# P14_Hi3531AV100_SATA_PC.net
KiCad netlist of a schematic drawn in Altium Designer
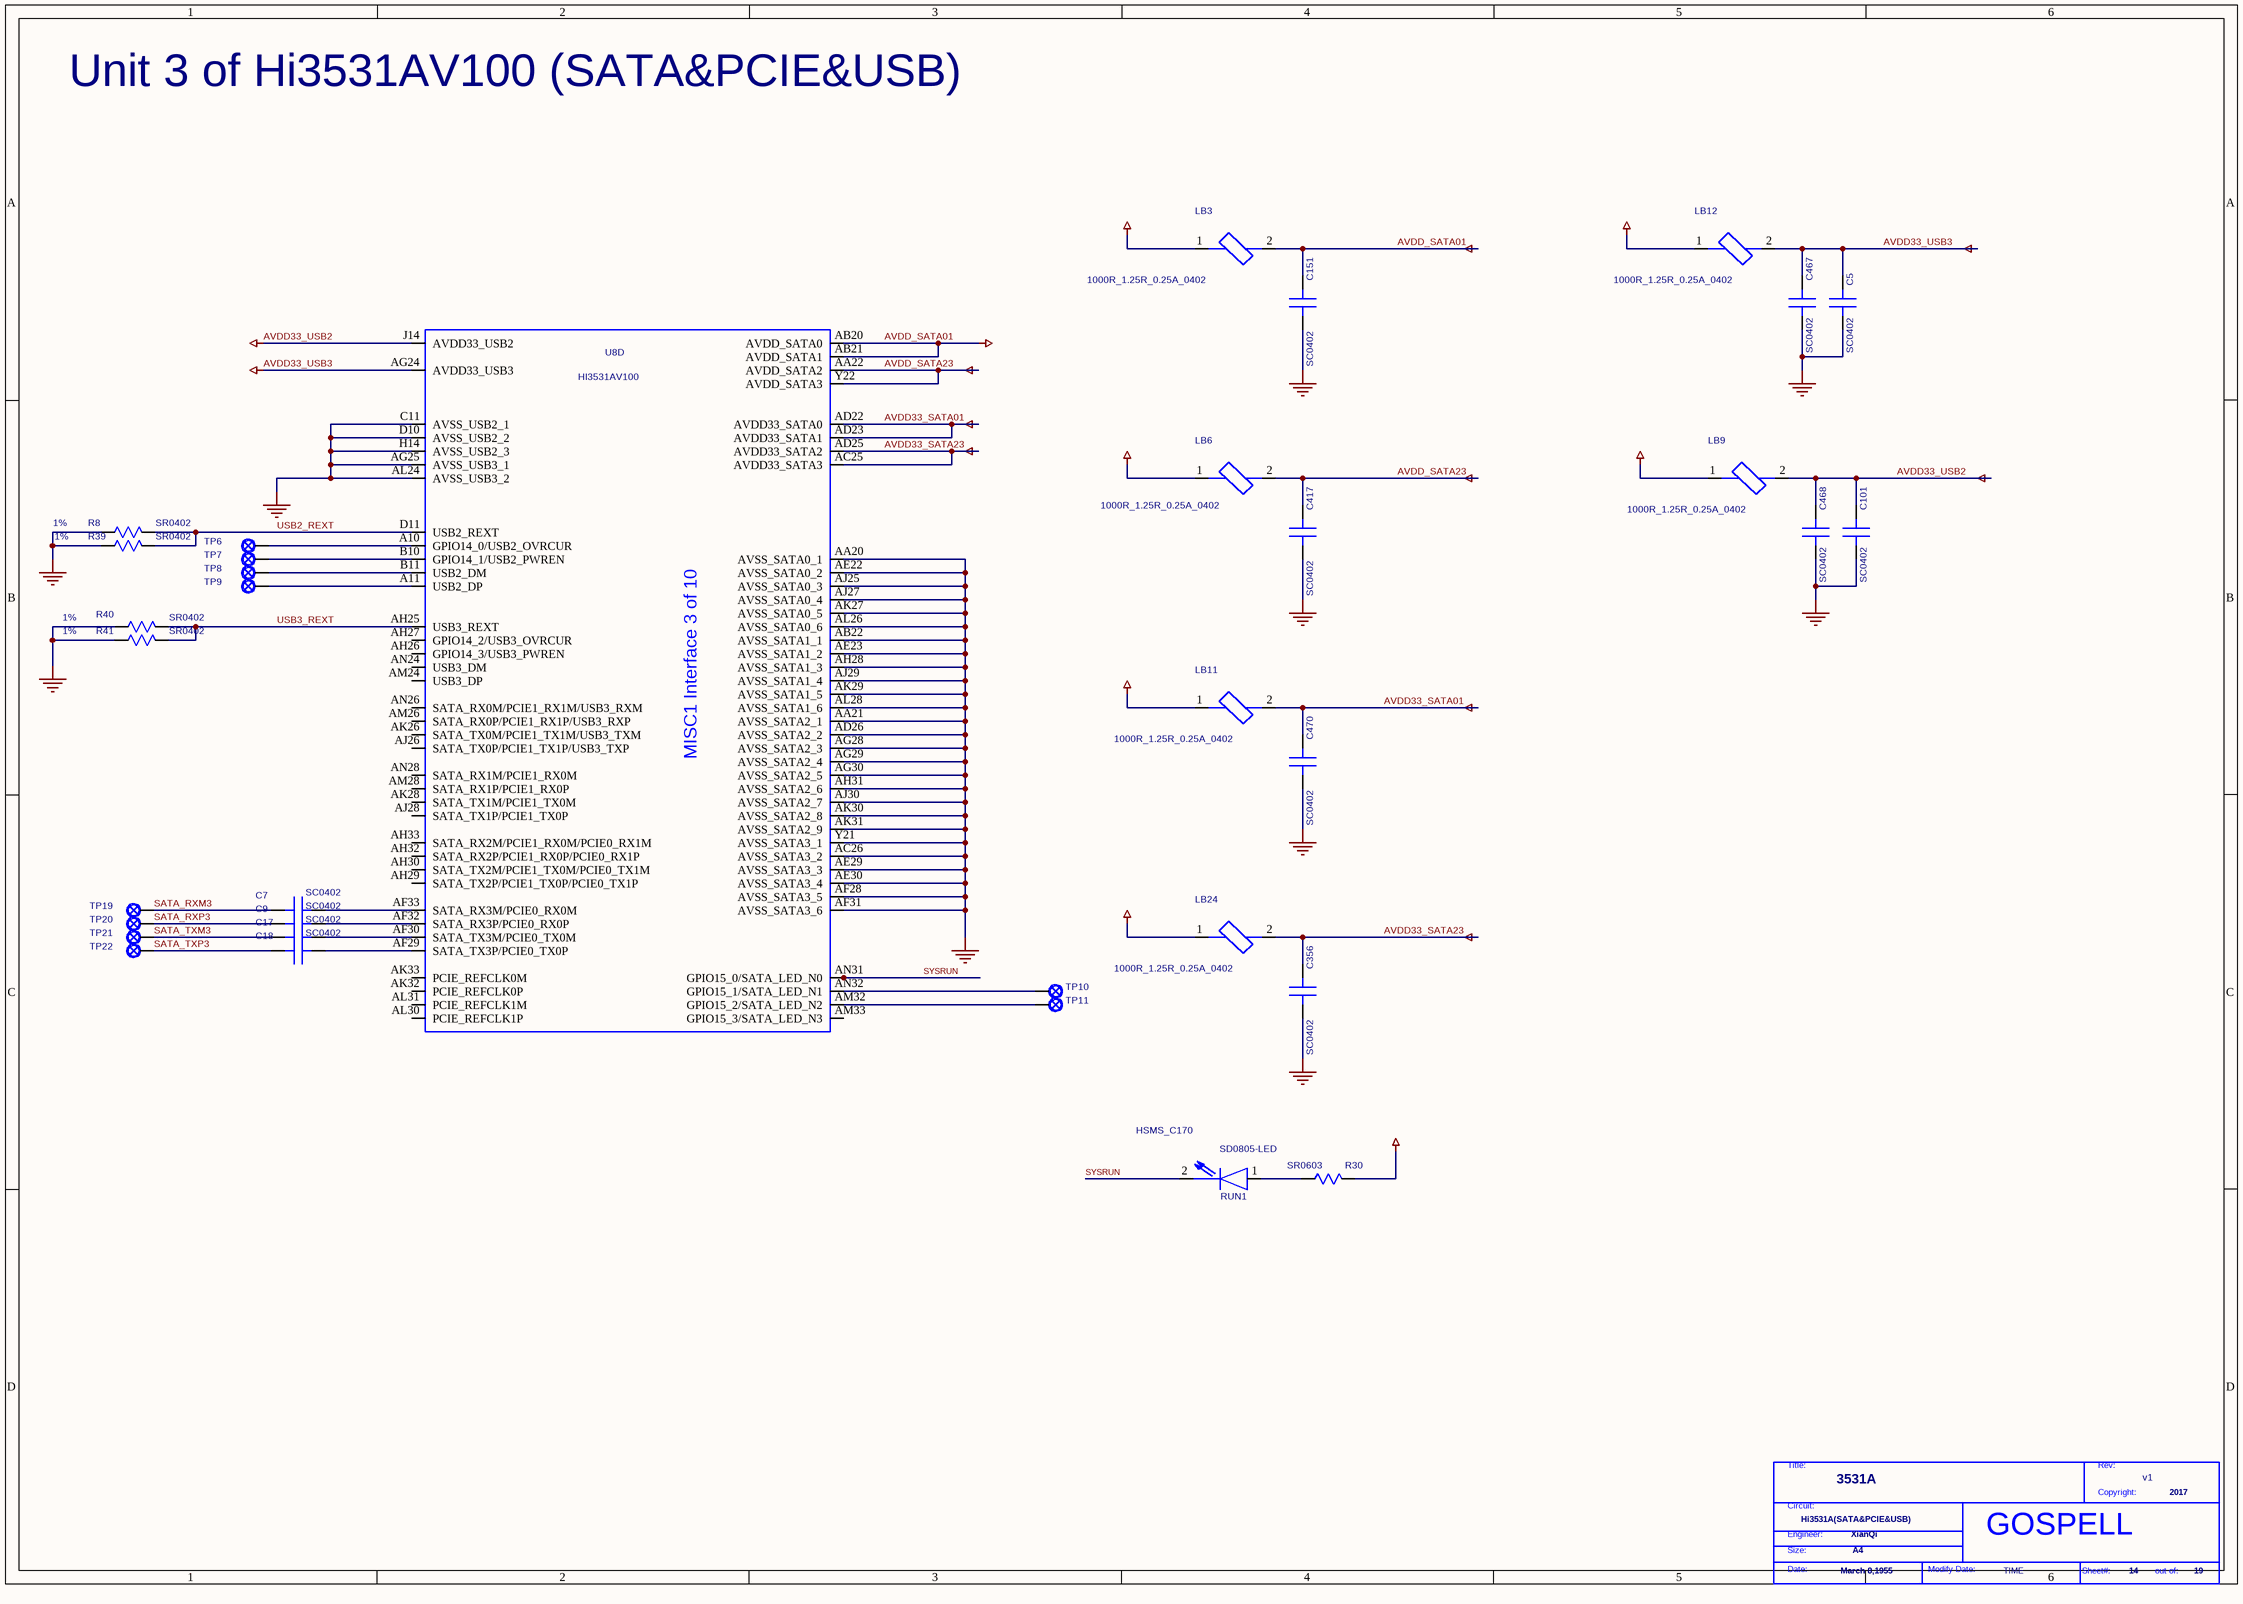
[diagram p0: P14 Hi3531AV100(SATA&PC.SchDoc]

(export (version "E")
  (design (tool "Eeschema 10.0.6"))
  (components
    (comp (ref "C5") (value "SC0402") (libsource (lib "*") (part "C_0_Dup2")))
    (comp (ref "C7") (value "SC0402") (libsource (lib "*") (part "C_0_Dup2")))
    (comp (ref "C9") (value "SC0402") (libsource (lib "*") (part "C_0_Dup2")))
    (comp (ref "C17") (value "SC0402") (libsource (lib "*") (part "C_0_Dup2")))
    (comp (ref "C18") (value "SC0402") (libsource (lib "*") (part "C_0_Dup2")))
    (comp (ref "C101") (value "SC0402") (libsource (lib "*") (part "C_0_Dup2")))
    (comp (ref "C151") (value "SC0402") (libsource (lib "*") (part "C_0_Dup2")))
    (comp (ref "C356") (value "SC0402") (libsource (lib "*") (part "C_0_Dup2")))
    (comp (ref "C417") (value "SC0402") (libsource (lib "*") (part "C_0_Dup2")))
    (comp (ref "C467") (value "SC0402") (libsource (lib "*") (part "C_0_Dup2")))
    (comp (ref "C468") (value "SC0402") (libsource (lib "*") (part "C_0_Dup2")))
    (comp (ref "C470") (value "SC0402") (libsource (lib "*") (part "C_0_Dup2")))
    (comp (ref "LB3") (value "SL0402") (libsource (lib "*") (part "LB_0")))
    (comp (ref "LB6") (value "SL0402") (libsource (lib "*") (part "LB_0")))
    (comp (ref "LB9") (value "SL0402") (libsource (lib "*") (part "LB_0")))
    (comp (ref "LB11") (value "SL0402") (libsource (lib "*") (part "LB_0")))
    (comp (ref "LB12") (value "SL0402") (libsource (lib "*") (part "LB_0")))
    (comp (ref "LB24") (value "SL0402") (libsource (lib "*") (part "LB_0")))
    (comp (ref "R8") (value "SR0402") (libsource (lib "*") (part "R_1")))
    (comp (ref "R30") (value "SR0603") (libsource (lib "*") (part "R_1")))
    (comp (ref "R39") (value "SR0402") (libsource (lib "*") (part "R_1")))
    (comp (ref "R40") (value "SR0402") (libsource (lib "*") (part "R_1")))
    (comp (ref "R41") (value "SR0402") (libsource (lib "*") (part "R_1")))
    (comp (ref "RUN1")
      (value "SD0805-LED")
      (fields (field (name "DEVICE") "HSMS_C170"))
      (libsource (lib "*") (part "LED_1"))
    )
    (comp (ref "TP6") (value "TP24-SMD") (libsource (lib "*") (part "TESTPOINT_0")))
    (comp (ref "TP7") (value "TP24-SMD") (libsource (lib "*") (part "TESTPOINT_0")))
    (comp (ref "TP8") (value "TP24-SMD") (libsource (lib "*") (part "TESTPOINT_0")))
    (comp (ref "TP9") (value "TP24-SMD") (libsource (lib "*") (part "TESTPOINT_0")))
    (comp (ref "TP10") (value "TP24-SMD") (libsource (lib "*") (part "TESTPOINT_0")))
    (comp (ref "TP11") (value "TP24-SMD") (libsource (lib "*") (part "TESTPOINT_0")))
    (comp (ref "TP19") (value "TP24-SMD") (libsource (lib "*") (part "TESTPOINT_0")))
    (comp (ref "TP20") (value "TP24-SMD") (libsource (lib "*") (part "TESTPOINT_0")))
    (comp (ref "TP21") (value "TP24-SMD") (libsource (lib "*") (part "TESTPOINT_0")))
    (comp (ref "TP22") (value "TP24-SMD") (libsource (lib "*") (part "TESTPOINT_0")))
    (comp (ref "U8")
      (value "BGA805-32-3333")
      (fields (field (name "DEVICE") "HI3531AV100"))
      (libsource (lib "*") (part "HI3531AV100_M2_17"))
    )
  )
  (nets
    (net (code "1") (name "/SATA_RXM3") (class "Default")
      (node (ref "C7") (pin "1") (pinfunction "A_1") (pintype "passive"))
      (node (ref "TP19") (pin "1") (pinfunction "1_1") (pintype "passive"))
    )
    (net (code "2") (name "/SATA_RXP3") (class "Default")
      (node (ref "C9") (pin "1") (pinfunction "A_1") (pintype "passive"))
      (node (ref "TP20") (pin "1") (pinfunction "1_1") (pintype "passive"))
    )
    (net (code "3") (name "/SATA_TXM3") (class "Default")
      (node (ref "C17") (pin "1") (pinfunction "A_1") (pintype "passive"))
      (node (ref "TP21") (pin "1") (pinfunction "1_1") (pintype "passive"))
    )
    (net (code "4") (name "/SATA_TXP3") (class "Default")
      (node (ref "C18") (pin "1") (pinfunction "A_1") (pintype "passive"))
      (node (ref "TP22") (pin "1") (pinfunction "1_1") (pintype "passive"))
    )
    (net (code "5") (name "/SYSRUN") (class "Default")
      (node (ref "RUN1") (pin "2") (pinfunction "B_2") (pintype "passive"))
      (node (ref "U8") (pin "AN31") (pinfunction "GPIO15_0/SATA_LED_N0_AN31") (pintype "passive"))
    )
    (net (code "6") (name "/USB2_REXT") (class "Default")
      (node (ref "R39") (pin "2") (pinfunction "B_2") (pintype "passive"))
      (node (ref "R8") (pin "2") (pinfunction "B_2") (pintype "passive"))
      (node (ref "U8") (pin "D11") (pinfunction "USB2_REXT_D11") (pintype "passive"))
    )
    (net (code "7") (name "/USB3_REXT") (class "Default")
      (node (ref "R40") (pin "2") (pinfunction "B_2") (pintype "passive"))
      (node (ref "R41") (pin "2") (pinfunction "B_2") (pintype "passive"))
      (node (ref "U8") (pin "AH25") (pinfunction "USB3_REXT_AH25") (pintype "passive"))
    )
    (net (code "8") (name "3V3") (class "Default")
      (node (ref "LB11") (pin "1") (pinfunction "1_1") (pintype "passive"))
      (node (ref "LB12") (pin "1") (pinfunction "1_1") (pintype "passive"))
      (node (ref "LB24") (pin "1") (pinfunction "1_1") (pintype "passive"))
      (node (ref "LB9") (pin "1") (pinfunction "1_1") (pintype "passive"))
      (node (ref "R30") (pin "1") (pinfunction "A_1") (pintype "passive"))
    )
    (net (code "9") (name "AVDD33_SATA01") (class "Default")
      (node (ref "C470") (pin "1") (pinfunction "A_1") (pintype "passive"))
      (node (ref "LB11") (pin "2") (pinfunction "2_2") (pintype "passive"))
      (node (ref "U8") (pin "AD22") (pinfunction "AVDD33_SATA0_AD22") (pintype "passive"))
      (node (ref "U8") (pin "AD23") (pinfunction "AVDD33_SATA1_AD23") (pintype "passive"))
    )
    (net (code "10") (name "AVDD33_SATA23") (class "Default")
      (node (ref "C356") (pin "1") (pinfunction "A_1") (pintype "passive"))
      (node (ref "LB24") (pin "2") (pinfunction "2_2") (pintype "passive"))
      (node (ref "U8") (pin "AC25") (pinfunction "AVDD33_SATA3_AC25") (pintype "passive"))
      (node (ref "U8") (pin "AD25") (pinfunction "AVDD33_SATA2_AD25") (pintype "passive"))
    )
    (net (code "11") (name "AVDD33_USB2") (class "Default")
      (node (ref "C101") (pin "1") (pinfunction "A_1") (pintype "passive"))
      (node (ref "C468") (pin "1") (pinfunction "A_1") (pintype "passive"))
      (node (ref "LB9") (pin "2") (pinfunction "2_2") (pintype "passive"))
      (node (ref "U8") (pin "J14") (pinfunction "AVDD33_USB2_J14") (pintype "passive"))
    )
    (net (code "12") (name "AVDD33_USB3") (class "Default")
      (node (ref "C467") (pin "1") (pinfunction "A_1") (pintype "passive"))
      (node (ref "C5") (pin "1") (pinfunction "A_1") (pintype "passive"))
      (node (ref "LB12") (pin "2") (pinfunction "2_2") (pintype "passive"))
      (node (ref "U8") (pin "AG24") (pinfunction "AVDD33_USB3_AG24") (pintype "passive"))
    )
    (net (code "13") (name "AVDD_SATA01") (class "Default")
      (node (ref "C151") (pin "1") (pinfunction "A_1") (pintype "passive"))
      (node (ref "LB3") (pin "2") (pinfunction "2_2") (pintype "passive"))
      (node (ref "U8") (pin "AB20") (pinfunction "AVDD_SATA0_AB20") (pintype "passive"))
      (node (ref "U8") (pin "AB21") (pinfunction "AVDD_SATA1_AB21") (pintype "passive"))
    )
    (net (code "14") (name "AVDD_SATA23") (class "Default")
      (node (ref "C417") (pin "1") (pinfunction "A_1") (pintype "passive"))
      (node (ref "LB6") (pin "2") (pinfunction "2_2") (pintype "passive"))
      (node (ref "U8") (pin "AA22") (pinfunction "AVDD_SATA2_AA22") (pintype "passive"))
      (node (ref "U8") (pin "Y22") (pinfunction "AVDD_SATA3_Y22") (pintype "passive"))
    )
    (net (code "15") (name "DVDD_CORE") (class "Default")
      (node (ref "LB3") (pin "1") (pinfunction "1_1") (pintype "passive"))
      (node (ref "LB6") (pin "1") (pinfunction "1_1") (pintype "passive"))
    )
    (net (code "16") (name "GND") (class "Default")
      (node (ref "C101") (pin "2") (pinfunction "B_2") (pintype "passive"))
      (node (ref "C151") (pin "2") (pinfunction "B_2") (pintype "passive"))
      (node (ref "C356") (pin "2") (pinfunction "B_2") (pintype "passive"))
      (node (ref "C417") (pin "2") (pinfunction "B_2") (pintype "passive"))
      (node (ref "C467") (pin "2") (pinfunction "B_2") (pintype "passive"))
      (node (ref "C468") (pin "2") (pinfunction "B_2") (pintype "passive"))
      (node (ref "C470") (pin "2") (pinfunction "B_2") (pintype "passive"))
      (node (ref "C5") (pin "2") (pinfunction "B_2") (pintype "passive"))
      (node (ref "R39") (pin "1") (pinfunction "A_1") (pintype "passive"))
      (node (ref "R40") (pin "1") (pinfunction "A_1") (pintype "passive"))
      (node (ref "R41") (pin "1") (pinfunction "A_1") (pintype "passive"))
      (node (ref "R8") (pin "1") (pinfunction "A_1") (pintype "passive"))
      (node (ref "U8") (pin "AA20") (pinfunction "AVSS_SATA0_1_AA20") (pintype "passive"))
      (node (ref "U8") (pin "AA21") (pinfunction "AVSS_SATA2_1_AA21") (pintype "passive"))
      (node (ref "U8") (pin "AB22") (pinfunction "AVSS_SATA1_1_AB22") (pintype "passive"))
      (node (ref "U8") (pin "AC26") (pinfunction "AVSS_SATA3_2_AC26") (pintype "passive"))
      (node (ref "U8") (pin "AD26") (pinfunction "AVSS_SATA2_2_AD26") (pintype "passive"))
      (node (ref "U8") (pin "AE22") (pinfunction "AVSS_SATA0_2_AE22") (pintype "passive"))
      (node (ref "U8") (pin "AE23") (pinfunction "AVSS_SATA1_2_AE23") (pintype "passive"))
      (node (ref "U8") (pin "AE29") (pinfunction "AVSS_SATA3_3_AE29") (pintype "passive"))
      (node (ref "U8") (pin "AE30") (pinfunction "AVSS_SATA3_4_AE30") (pintype "passive"))
      (node (ref "U8") (pin "AF28") (pinfunction "AVSS_SATA3_5_AF28") (pintype "passive"))
      (node (ref "U8") (pin "AF31") (pinfunction "AVSS_SATA3_6_AF31") (pintype "passive"))
      (node (ref "U8") (pin "AG25") (pinfunction "AVSS_USB3_1_AG25") (pintype "passive"))
      (node (ref "U8") (pin "AG28") (pinfunction "AVSS_SATA2_3_AG28") (pintype "passive"))
      (node (ref "U8") (pin "AG29") (pinfunction "AVSS_SATA2_4_AG29") (pintype "passive"))
      (node (ref "U8") (pin "AG30") (pinfunction "AVSS_SATA2_5_AG30") (pintype "passive"))
      (node (ref "U8") (pin "AH28") (pinfunction "AVSS_SATA1_3_AH28") (pintype "passive"))
      (node (ref "U8") (pin "AH31") (pinfunction "AVSS_SATA2_6_AH31") (pintype "passive"))
      (node (ref "U8") (pin "AJ25") (pinfunction "AVSS_SATA0_3_AJ25") (pintype "passive"))
      (node (ref "U8") (pin "AJ27") (pinfunction "AVSS_SATA0_4_AJ27") (pintype "passive"))
      (node (ref "U8") (pin "AJ29") (pinfunction "AVSS_SATA1_4_AJ29") (pintype "passive"))
      (node (ref "U8") (pin "AJ30") (pinfunction "AVSS_SATA2_7_AJ30") (pintype "passive"))
      (node (ref "U8") (pin "AK27") (pinfunction "AVSS_SATA0_5_AK27") (pintype "passive"))
      (node (ref "U8") (pin "AK29") (pinfunction "AVSS_SATA1_5_AK29") (pintype "passive"))
      (node (ref "U8") (pin "AK30") (pinfunction "AVSS_SATA2_8_AK30") (pintype "passive"))
      (node (ref "U8") (pin "AK31") (pinfunction "AVSS_SATA2_9_AK31") (pintype "passive"))
      (node (ref "U8") (pin "AL24") (pinfunction "AVSS_USB3_2_AL24") (pintype "passive"))
      (node (ref "U8") (pin "AL26") (pinfunction "AVSS_SATA0_6_AL26") (pintype "passive"))
      (node (ref "U8") (pin "AL28") (pinfunction "AVSS_SATA1_6_AL28") (pintype "passive"))
      (node (ref "U8") (pin "C11") (pinfunction "AVSS_USB2_1_C11") (pintype "passive"))
      (node (ref "U8") (pin "D10") (pinfunction "AVSS_USB2_2_D10") (pintype "passive"))
      (node (ref "U8") (pin "H14") (pinfunction "AVSS_USB2_3_H14") (pintype "passive"))
      (node (ref "U8") (pin "Y21") (pinfunction "AVSS_SATA3_1_Y21") (pintype "passive"))
    )
    (net (code "17") (name "Net-(C7-B)") (class "Default")
      (node (ref "C7") (pin "2") (pinfunction "B_2") (pintype "passive"))
      (node (ref "U8") (pin "AF33") (pinfunction "SATA_RX3M/PCIE0_RX0M_AF33") (pintype "passive"))
    )
    (net (code "18") (name "Net-(C9-B)") (class "Default")
      (node (ref "C9") (pin "2") (pinfunction "B_2") (pintype "passive"))
      (node (ref "U8") (pin "AF32") (pinfunction "SATA_RX3P/PCIE0_RX0P_AF32") (pintype "passive"))
    )
    (net (code "19") (name "Net-(C17-B)") (class "Default")
      (node (ref "C17") (pin "2") (pinfunction "B_2") (pintype "passive"))
      (node (ref "U8") (pin "AF30") (pinfunction "SATA_TX3M/PCIE0_TX0M_AF30") (pintype "passive"))
    )
    (net (code "20") (name "Net-(C18-B)") (class "Default")
      (node (ref "C18") (pin "2") (pinfunction "B_2") (pintype "passive"))
      (node (ref "U8") (pin "AF29") (pinfunction "SATA_TX3P/PCIE0_TX0P_AF29") (pintype "passive"))
    )
    (net (code "21") (name "Net-(R30-B)") (class "Default")
      (node (ref "R30") (pin "2") (pinfunction "B_2") (pintype "passive"))
      (node (ref "RUN1") (pin "1") (pinfunction "A_1") (pintype "passive"))
    )
    (net (code "22") (name "Net-(U8D-GPIO14_0{slash}USB2_OVRCUR)") (class "Default")
      (node (ref "TP6") (pin "1") (pinfunction "1_1") (pintype "passive"))
      (node (ref "U8") (pin "A10") (pinfunction "GPIO14_0/USB2_OVRCUR_A10") (pintype "passive"))
    )
    (net (code "23") (name "Net-(U8D-GPIO14_1{slash}USB2_PWREN)") (class "Default")
      (node (ref "TP7") (pin "1") (pinfunction "1_1") (pintype "passive"))
      (node (ref "U8") (pin "B10") (pinfunction "GPIO14_1/USB2_PWREN_B10") (pintype "passive"))
    )
    (net (code "24") (name "Net-(U8D-GPIO15_1{slash}SATA_LED_N1)") (class "Default")
      (node (ref "TP10") (pin "1") (pinfunction "1_1") (pintype "passive"))
      (node (ref "U8") (pin "AN32") (pinfunction "GPIO15_1/SATA_LED_N1_AN32") (pintype "passive"))
    )
    (net (code "25") (name "Net-(U8D-GPIO15_2{slash}SATA_LED_N2)") (class "Default")
      (node (ref "TP11") (pin "1") (pinfunction "1_1") (pintype "passive"))
      (node (ref "U8") (pin "AM32") (pinfunction "GPIO15_2/SATA_LED_N2_AM32") (pintype "passive"))
    )
    (net (code "26") (name "Net-(U8D-USB2_DM)") (class "Default")
      (node (ref "TP8") (pin "1") (pinfunction "1_1") (pintype "passive"))
      (node (ref "U8") (pin "B11") (pinfunction "USB2_DM_B11") (pintype "passive"))
    )
    (net (code "27") (name "Net-(U8D-USB2_DP)") (class "Default")
      (node (ref "TP9") (pin "1") (pinfunction "1_1") (pintype "passive"))
      (node (ref "U8") (pin "A11") (pinfunction "USB2_DP_A11") (pintype "passive"))
    )
    (net (code "28") (name "unconnected-(U8D-GPIO14_2{slash}USB3_OVRCUR-PadAH27)") (class "Default")
      (node (ref "U8") (pin "AH27") (pinfunction "GPIO14_2/USB3_OVRCUR_AH27") (pintype "passive"))
    )
    (net (code "29") (name "unconnected-(U8D-GPIO14_3{slash}USB3_PWREN-PadAH26)") (class "Default")
      (node (ref "U8") (pin "AH26") (pinfunction "GPIO14_3/USB3_PWREN_AH26") (pintype "passive"))
    )
    (net (code "30") (name "unconnected-(U8D-GPIO15_3{slash}SATA_LED_N3-PadAM33)") (class "Default")
      (node (ref "U8") (pin "AM33") (pinfunction "GPIO15_3/SATA_LED_N3_AM33") (pintype "passive"))
    )
    (net (code "31") (name "unconnected-(U8D-PCIE_REFCLK0M-PadAK33)") (class "Default")
      (node (ref "U8") (pin "AK33") (pinfunction "PCIE_REFCLK0M_AK33") (pintype "passive"))
    )
    (net (code "32") (name "unconnected-(U8D-PCIE_REFCLK0P-PadAK32)") (class "Default")
      (node (ref "U8") (pin "AK32") (pinfunction "PCIE_REFCLK0P_AK32") (pintype "passive"))
    )
    (net (code "33") (name "unconnected-(U8D-PCIE_REFCLK1M-PadAL31)") (class "Default")
      (node (ref "U8") (pin "AL31") (pinfunction "PCIE_REFCLK1M_AL31") (pintype "passive"))
    )
    (net (code "34") (name "unconnected-(U8D-PCIE_REFCLK1P-PadAL30)") (class "Default")
      (node (ref "U8") (pin "AL30") (pinfunction "PCIE_REFCLK1P_AL30") (pintype "passive"))
    )
    (net (code "35") (name "unconnected-(U8D-SATA_RX0M{slash}PCIE1_RX1M{slash}USB3_RXM-PadAN26)") (class "Default")
      (node (ref "U8") (pin "AN26") (pinfunction "SATA_RX0M/PCIE1_RX1M/USB3_RXM_AN26") (pintype "passive"))
    )
    (net (code "36") (name "unconnected-(U8D-SATA_RX0P{slash}PCIE1_RX1P{slash}USB3_RXP-PadAM26)") (class "Default")
      (node (ref "U8") (pin "AM26") (pinfunction "SATA_RX0P/PCIE1_RX1P/USB3_RXP_AM26") (pintype "passive"))
    )
    (net (code "37") (name "unconnected-(U8D-SATA_RX1M{slash}PCIE1_RX0M-PadAN28)") (class "Default")
      (node (ref "U8") (pin "AN28") (pinfunction "SATA_RX1M/PCIE1_RX0M_AN28") (pintype "passive"))
    )
    (net (code "38") (name "unconnected-(U8D-SATA_RX1P{slash}PCIE1_RX0P-PadAM28)") (class "Default")
      (node (ref "U8") (pin "AM28") (pinfunction "SATA_RX1P/PCIE1_RX0P_AM28") (pintype "passive"))
    )
    (net (code "39") (name "unconnected-(U8D-SATA_RX2M{slash}PCIE1_RX0M{slash}PCIE0_RX1M-PadAH33)") (class "Default")
      (node (ref "U8") (pin "AH33") (pinfunction "SATA_RX2M/PCIE1_RX0M/PCIE0_RX1M_AH33") (pintype "passive"))
    )
    (net (code "40") (name "unconnected-(U8D-SATA_RX2P{slash}PCIE1_RX0P{slash}PCIE0_RX1P-PadAH32)") (class "Default")
      (node (ref "U8") (pin "AH32") (pinfunction "SATA_RX2P/PCIE1_RX0P/PCIE0_RX1P_AH32") (pintype "passive"))
    )
    (net (code "41") (name "unconnected-(U8D-SATA_TX0M{slash}PCIE1_TX1M{slash}USB3_TXM-PadAK26)") (class "Default")
      (node (ref "U8") (pin "AK26") (pinfunction "SATA_TX0M/PCIE1_TX1M/USB3_TXM_AK26") (pintype "passive"))
    )
    (net (code "42") (name "unconnected-(U8D-SATA_TX0P{slash}PCIE1_TX1P{slash}USB3_TXP-PadAJ26)") (class "Default")
      (node (ref "U8") (pin "AJ26") (pinfunction "SATA_TX0P/PCIE1_TX1P/USB3_TXP_AJ26") (pintype "passive"))
    )
    (net (code "43") (name "unconnected-(U8D-SATA_TX1M{slash}PCIE1_TX0M-PadAK28)") (class "Default")
      (node (ref "U8") (pin "AK28") (pinfunction "SATA_TX1M/PCIE1_TX0M_AK28") (pintype "passive"))
    )
    (net (code "44") (name "unconnected-(U8D-SATA_TX1P{slash}PCIE1_TX0P-PadAJ28)") (class "Default")
      (node (ref "U8") (pin "AJ28") (pinfunction "SATA_TX1P/PCIE1_TX0P_AJ28") (pintype "passive"))
    )
    (net (code "45") (name "unconnected-(U8D-SATA_TX2M{slash}PCIE1_TX0M{slash}PCIE0_TX1M-PadAH30)") (class "Default")
      (node (ref "U8") (pin "AH30") (pinfunction "SATA_TX2M/PCIE1_TX0M/PCIE0_TX1M_AH30") (pintype "passive"))
    )
    (net (code "46") (name "unconnected-(U8D-SATA_TX2P{slash}PCIE1_TX0P{slash}PCIE0_TX1P-PadAH29)") (class "Default")
      (node (ref "U8") (pin "AH29") (pinfunction "SATA_TX2P/PCIE1_TX0P/PCIE0_TX1P_AH29") (pintype "passive"))
    )
    (net (code "47") (name "unconnected-(U8D-USB3_DM-PadAN24)") (class "Default")
      (node (ref "U8") (pin "AN24") (pinfunction "USB3_DM_AN24") (pintype "passive"))
    )
    (net (code "48") (name "unconnected-(U8D-USB3_DP-PadAM24)") (class "Default")
      (node (ref "U8") (pin "AM24") (pinfunction "USB3_DP_AM24") (pintype "passive"))
    )
  )
)
